# GucciMain.net
KiCad netlist of a schematic drawn in EAGLE
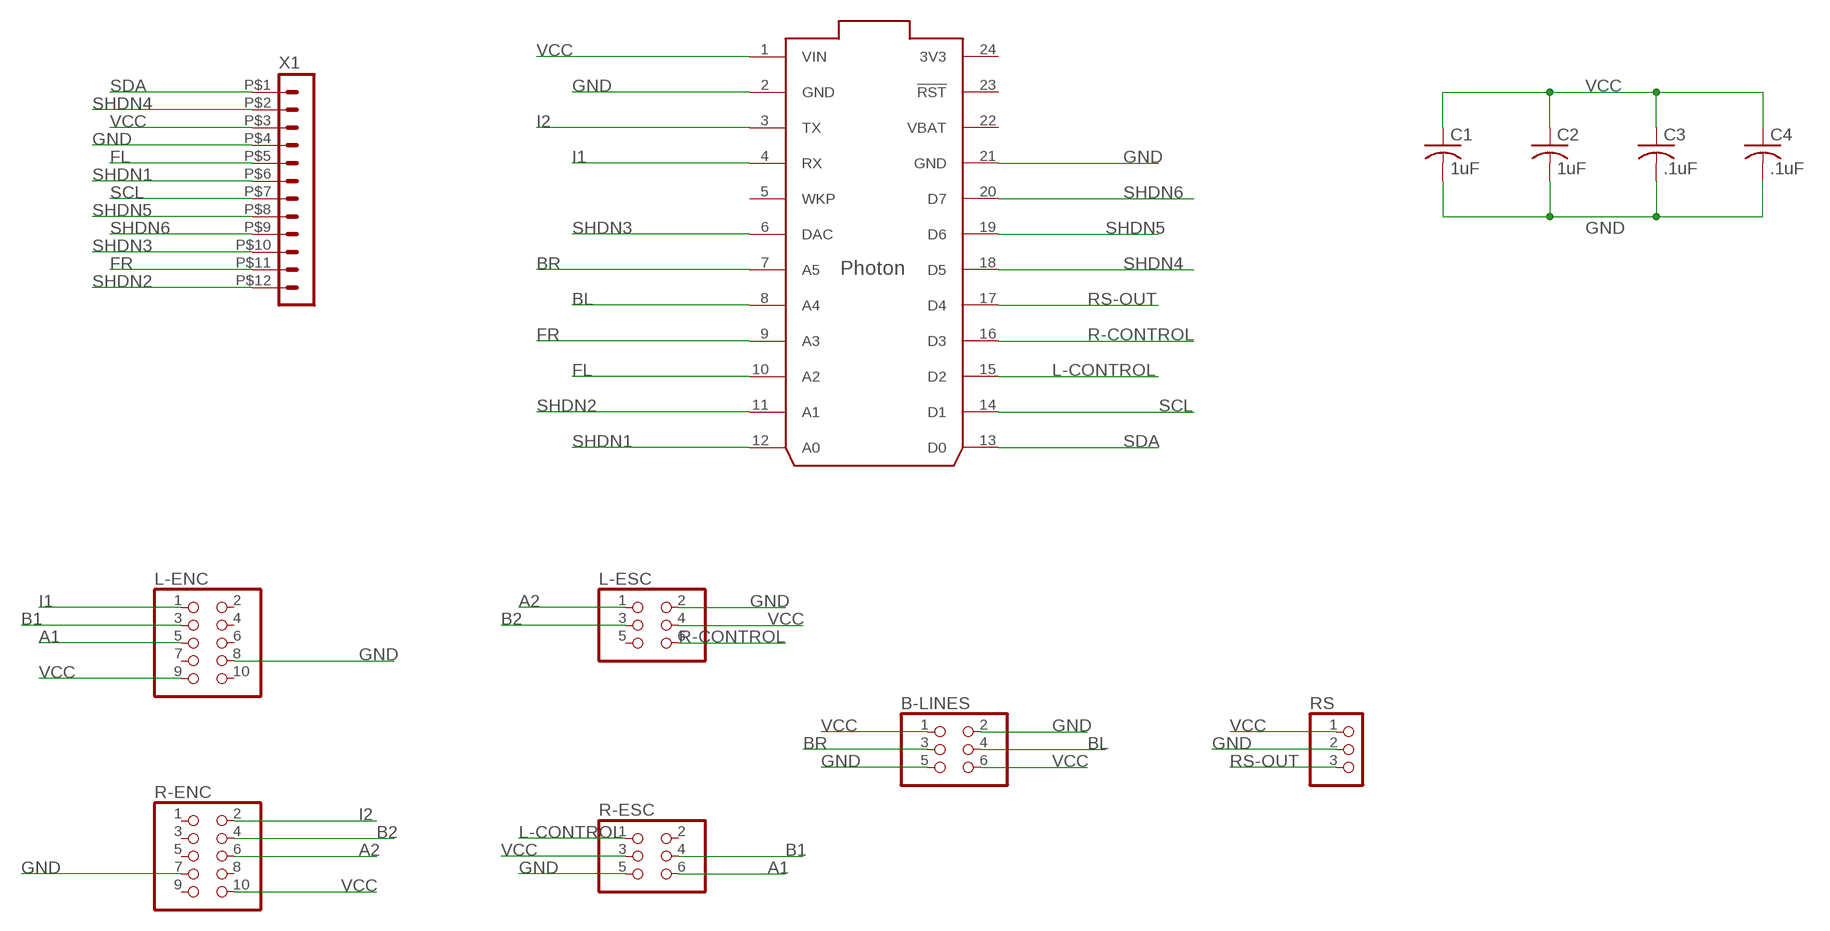
[diagram p0: schematic, sheet 1]

(export (version "E")
  (design (tool "Eeschema 10.0.6"))
  (components
    (comp (ref "B-LINES")
      (value "PINHD-2X3/90")
      (footprint "eagle-import:2X03_90")
      (libsource (lib "eagle-import") (part "PINHD-2X3/90"))
    )
    (comp (ref "C1")
      (value "1uF")
      (footprint "eagle-import:C0402")
      (libsource (lib "eagle-import") (part "C-USC0402"))
    )
    (comp (ref "C2")
      (value "1uF")
      (footprint "eagle-import:C0402")
      (libsource (lib "eagle-import") (part "C-USC0402"))
    )
    (comp (ref "C3")
      (value ".1uF")
      (footprint "eagle-import:C0402")
      (libsource (lib "eagle-import") (part "C-USC0402"))
    )
    (comp (ref "C4")
      (value ".1uF")
      (footprint "eagle-import:C0402")
      (libsource (lib "eagle-import") (part "C-USC0402"))
    )
    (comp (ref "L-ENC")
      (value "PINHD-2X5/90")
      (footprint "eagle-import:2X05_90")
      (libsource (lib "eagle-import") (part "PINHD-2X5/90"))
    )
    (comp (ref "L-ESC")
      (value "PINHD-2X3")
      (footprint "eagle-import:2X03")
      (libsource (lib "eagle-import") (part "PINHD-2X3"))
    )
    (comp (ref "PHOTON")
      (value "PHOTON")
      (footprint "eagle-import:PHOTON")
      (libsource (lib "eagle-import") (part "PHOTON_WITH_HEADERS"))
    )
    (comp (ref "R-ENC")
      (value "PINHD-2X5/90")
      (footprint "eagle-import:2X05_90")
      (libsource (lib "eagle-import") (part "PINHD-2X5/90"))
    )
    (comp (ref "R-ESC")
      (value "PINHD-2X3")
      (footprint "eagle-import:2X03")
      (libsource (lib "eagle-import") (part "PINHD-2X3"))
    )
    (comp (ref "RS")
      (value "PINHD-1X3")
      (footprint "eagle-import:1X03")
      (libsource (lib "eagle-import") (part "PINHD-1X3"))
    )
    (comp (ref "X1")
      (value "HEADER_POS12_43045-1212")
      (footprint "eagle-import:43045-1212")
      (libsource (lib "eagle-import") (part "HEADER_POS12_?43045-1212"))
    )
  )
  (nets
    (net (code "1") (name "/3V3") (class "Default")
      (node (ref "PHOTON") (pin "24") (pinfunction "3V3_24") (pintype "power_in"))
    )
    (net (code "2") (name "/A1") (class "Default")
      (node (ref "L-ENC") (pin "5") (pinfunction "5_5") (pintype "passive"))
      (node (ref "R-ESC") (pin "6") (pinfunction "6_6") (pintype "passive"))
    )
    (net (code "3") (name "/A2") (class "Default")
      (node (ref "L-ESC") (pin "1") (pinfunction "1_1") (pintype "passive"))
      (node (ref "R-ENC") (pin "6") (pinfunction "6_6") (pintype "passive"))
    )
    (net (code "4") (name "/B1") (class "Default")
      (node (ref "L-ENC") (pin "3") (pinfunction "3_3") (pintype "passive"))
      (node (ref "R-ESC") (pin "4") (pinfunction "4_4") (pintype "passive"))
    )
    (net (code "5") (name "/B2") (class "Default")
      (node (ref "L-ESC") (pin "3") (pinfunction "3_3") (pintype "passive"))
      (node (ref "R-ENC") (pin "4") (pinfunction "4_4") (pintype "passive"))
    )
    (net (code "6") (name "/BL") (class "Default")
      (node (ref "B-LINES") (pin "4") (pinfunction "4_4") (pintype "passive"))
      (node (ref "PHOTON") (pin "8") (pinfunction "A4_8") (pintype "bidirectional"))
    )
    (net (code "7") (name "/BR") (class "Default")
      (node (ref "B-LINES") (pin "3") (pinfunction "3_3") (pintype "passive"))
      (node (ref "PHOTON") (pin "7") (pinfunction "A5_7") (pintype "bidirectional"))
    )
    (net (code "8") (name "/FL") (class "Default")
      (node (ref "PHOTON") (pin "10") (pinfunction "A2_10") (pintype "bidirectional"))
      (node (ref "X1") (pin "P$5") (pinfunction "5_P$5") (pintype "passive"))
    )
    (net (code "9") (name "/FR") (class "Default")
      (node (ref "PHOTON") (pin "9") (pinfunction "A3_9") (pintype "bidirectional"))
      (node (ref "X1") (pin "P$11") (pinfunction "11_P$11") (pintype "passive"))
    )
    (net (code "10") (name "/GND") (class "Default")
      (node (ref "B-LINES") (pin "2") (pinfunction "2_2") (pintype "passive"))
      (node (ref "B-LINES") (pin "5") (pinfunction "5_5") (pintype "passive"))
      (node (ref "C1") (pin "2") (pinfunction "2_2") (pintype "passive"))
      (node (ref "C2") (pin "2") (pinfunction "2_2") (pintype "passive"))
      (node (ref "C3") (pin "2") (pinfunction "2_2") (pintype "passive"))
      (node (ref "C4") (pin "2") (pinfunction "2_2") (pintype "passive"))
      (node (ref "L-ENC") (pin "8") (pinfunction "8_8") (pintype "passive"))
      (node (ref "L-ESC") (pin "2") (pinfunction "2_2") (pintype "passive"))
      (node (ref "PHOTON") (pin "2") (pinfunction "GND_2") (pintype "power_in"))
      (node (ref "PHOTON") (pin "21") (pinfunction "GND_21") (pintype "power_in"))
      (node (ref "R-ENC") (pin "7") (pinfunction "7_7") (pintype "passive"))
      (node (ref "R-ESC") (pin "5") (pinfunction "5_5") (pintype "passive"))
      (node (ref "RS") (pin "2") (pinfunction "2_2") (pintype "passive"))
      (node (ref "X1") (pin "P$4") (pinfunction "4_P$4") (pintype "passive"))
    )
    (net (code "11") (name "/I1") (class "Default")
      (node (ref "L-ENC") (pin "1") (pinfunction "1_1") (pintype "passive"))
      (node (ref "PHOTON") (pin "4") (pinfunction "RX_4") (pintype "bidirectional"))
    )
    (net (code "12") (name "/I2") (class "Default")
      (node (ref "PHOTON") (pin "3") (pinfunction "TX_3") (pintype "bidirectional"))
      (node (ref "R-ENC") (pin "2") (pinfunction "2_2") (pintype "passive"))
    )
    (net (code "13") (name "/L-CONTROL") (class "Default")
      (node (ref "PHOTON") (pin "15") (pinfunction "D2_15") (pintype "bidirectional"))
      (node (ref "R-ESC") (pin "1") (pinfunction "1_1") (pintype "passive"))
    )
    (net (code "14") (name "/R-CONTROL") (class "Default")
      (node (ref "L-ESC") (pin "6") (pinfunction "6_6") (pintype "passive"))
      (node (ref "PHOTON") (pin "16") (pinfunction "D3_16") (pintype "bidirectional"))
    )
    (net (code "15") (name "/RS-OUT") (class "Default")
      (node (ref "PHOTON") (pin "17") (pinfunction "D4_17") (pintype "bidirectional"))
      (node (ref "RS") (pin "3") (pinfunction "3_3") (pintype "passive"))
    )
    (net (code "16") (name "/SCL") (class "Default")
      (node (ref "PHOTON") (pin "14") (pinfunction "D1_14") (pintype "bidirectional"))
      (node (ref "X1") (pin "P$7") (pinfunction "7_P$7") (pintype "passive"))
    )
    (net (code "17") (name "/SDA") (class "Default")
      (node (ref "PHOTON") (pin "13") (pinfunction "D0_13") (pintype "bidirectional"))
      (node (ref "X1") (pin "P$1") (pinfunction "1_P$1") (pintype "passive"))
    )
    (net (code "18") (name "/SHDN1") (class "Default")
      (node (ref "PHOTON") (pin "12") (pinfunction "A0_12") (pintype "bidirectional"))
      (node (ref "X1") (pin "P$6") (pinfunction "6_P$6") (pintype "passive"))
    )
    (net (code "19") (name "/SHDN2") (class "Default")
      (node (ref "PHOTON") (pin "11") (pinfunction "A1_11") (pintype "bidirectional"))
      (node (ref "X1") (pin "P$12") (pinfunction "12_P$12") (pintype "passive"))
    )
    (net (code "20") (name "/SHDN3") (class "Default")
      (node (ref "PHOTON") (pin "6") (pinfunction "DAC_6") (pintype "bidirectional"))
      (node (ref "X1") (pin "P$10") (pinfunction "10_P$10") (pintype "passive"))
    )
    (net (code "21") (name "/SHDN4") (class "Default")
      (node (ref "PHOTON") (pin "18") (pinfunction "D5_18") (pintype "bidirectional"))
      (node (ref "X1") (pin "P$2") (pinfunction "2_P$2") (pintype "passive"))
    )
    (net (code "22") (name "/SHDN5") (class "Default")
      (node (ref "PHOTON") (pin "19") (pinfunction "D6_19") (pintype "bidirectional"))
      (node (ref "X1") (pin "P$8") (pinfunction "8_P$8") (pintype "passive"))
    )
    (net (code "23") (name "/SHDN6") (class "Default")
      (node (ref "PHOTON") (pin "20") (pinfunction "D7_20") (pintype "bidirectional"))
      (node (ref "X1") (pin "P$9") (pinfunction "9_P$9") (pintype "passive"))
    )
    (net (code "24") (name "/VBAT") (class "Default")
      (node (ref "PHOTON") (pin "22") (pinfunction "VBAT_22") (pintype "power_in"))
    )
    (net (code "25") (name "/VCC") (class "Default")
      (node (ref "B-LINES") (pin "1") (pinfunction "1_1") (pintype "passive"))
      (node (ref "B-LINES") (pin "6") (pinfunction "6_6") (pintype "passive"))
      (node (ref "C1") (pin "1") (pinfunction "1_1") (pintype "passive"))
      (node (ref "C2") (pin "1") (pinfunction "1_1") (pintype "passive"))
      (node (ref "C3") (pin "1") (pinfunction "1_1") (pintype "passive"))
      (node (ref "C4") (pin "1") (pinfunction "1_1") (pintype "passive"))
      (node (ref "L-ENC") (pin "9") (pinfunction "9_9") (pintype "passive"))
      (node (ref "L-ESC") (pin "4") (pinfunction "4_4") (pintype "passive"))
      (node (ref "PHOTON") (pin "1") (pinfunction "VIN_1") (pintype "power_in"))
      (node (ref "R-ENC") (pin "10") (pinfunction "10_10") (pintype "passive"))
      (node (ref "R-ESC") (pin "3") (pinfunction "3_3") (pintype "passive"))
      (node (ref "RS") (pin "1") (pinfunction "1_1") (pintype "passive"))
      (node (ref "X1") (pin "P$3") (pinfunction "3_P$3") (pintype "passive"))
    )
    (net (code "26") (name "unconnected-(L-ENC-Pad2)") (class "Default")
      (node (ref "L-ENC") (pin "2") (pinfunction "2_2") (pintype "passive"))
    )
    (net (code "27") (name "unconnected-(L-ENC-Pad4)") (class "Default")
      (node (ref "L-ENC") (pin "4") (pinfunction "4_4") (pintype "passive"))
    )
    (net (code "28") (name "unconnected-(L-ENC-Pad6)") (class "Default")
      (node (ref "L-ENC") (pin "6") (pinfunction "6_6") (pintype "passive"))
    )
    (net (code "29") (name "unconnected-(L-ENC-Pad7)") (class "Default")
      (node (ref "L-ENC") (pin "7") (pinfunction "7_7") (pintype "passive"))
    )
    (net (code "30") (name "unconnected-(L-ENC-Pad10)") (class "Default")
      (node (ref "L-ENC") (pin "10") (pinfunction "10_10") (pintype "passive"))
    )
    (net (code "31") (name "unconnected-(L-ESC-Pad5)") (class "Default")
      (node (ref "L-ESC") (pin "5") (pinfunction "5_5") (pintype "passive"))
    )
    (net (code "32") (name "unconnected-(PHOTON-WKP-Pad5)") (class "Default")
      (node (ref "PHOTON") (pin "5") (pinfunction "WKP_5") (pintype "bidirectional"))
    )
    (net (code "33") (name "unconnected-(PHOTON-~{RST}-Pad23)") (class "Default")
      (node (ref "PHOTON") (pin "23") (pinfunction "~{RST}_23") (pintype "bidirectional"))
    )
    (net (code "34") (name "unconnected-(R-ENC-Pad1)") (class "Default")
      (node (ref "R-ENC") (pin "1") (pinfunction "1_1") (pintype "passive"))
    )
    (net (code "35") (name "unconnected-(R-ENC-Pad3)") (class "Default")
      (node (ref "R-ENC") (pin "3") (pinfunction "3_3") (pintype "passive"))
    )
    (net (code "36") (name "unconnected-(R-ENC-Pad5)") (class "Default")
      (node (ref "R-ENC") (pin "5") (pinfunction "5_5") (pintype "passive"))
    )
    (net (code "37") (name "unconnected-(R-ENC-Pad8)") (class "Default")
      (node (ref "R-ENC") (pin "8") (pinfunction "8_8") (pintype "passive"))
    )
    (net (code "38") (name "unconnected-(R-ENC-Pad9)") (class "Default")
      (node (ref "R-ENC") (pin "9") (pinfunction "9_9") (pintype "passive"))
    )
    (net (code "39") (name "unconnected-(R-ESC-Pad2)") (class "Default")
      (node (ref "R-ESC") (pin "2") (pinfunction "2_2") (pintype "passive"))
    )
  )
)
